# Power_PCB.net
KiCad netlist of a schematic drawn in EAGLE
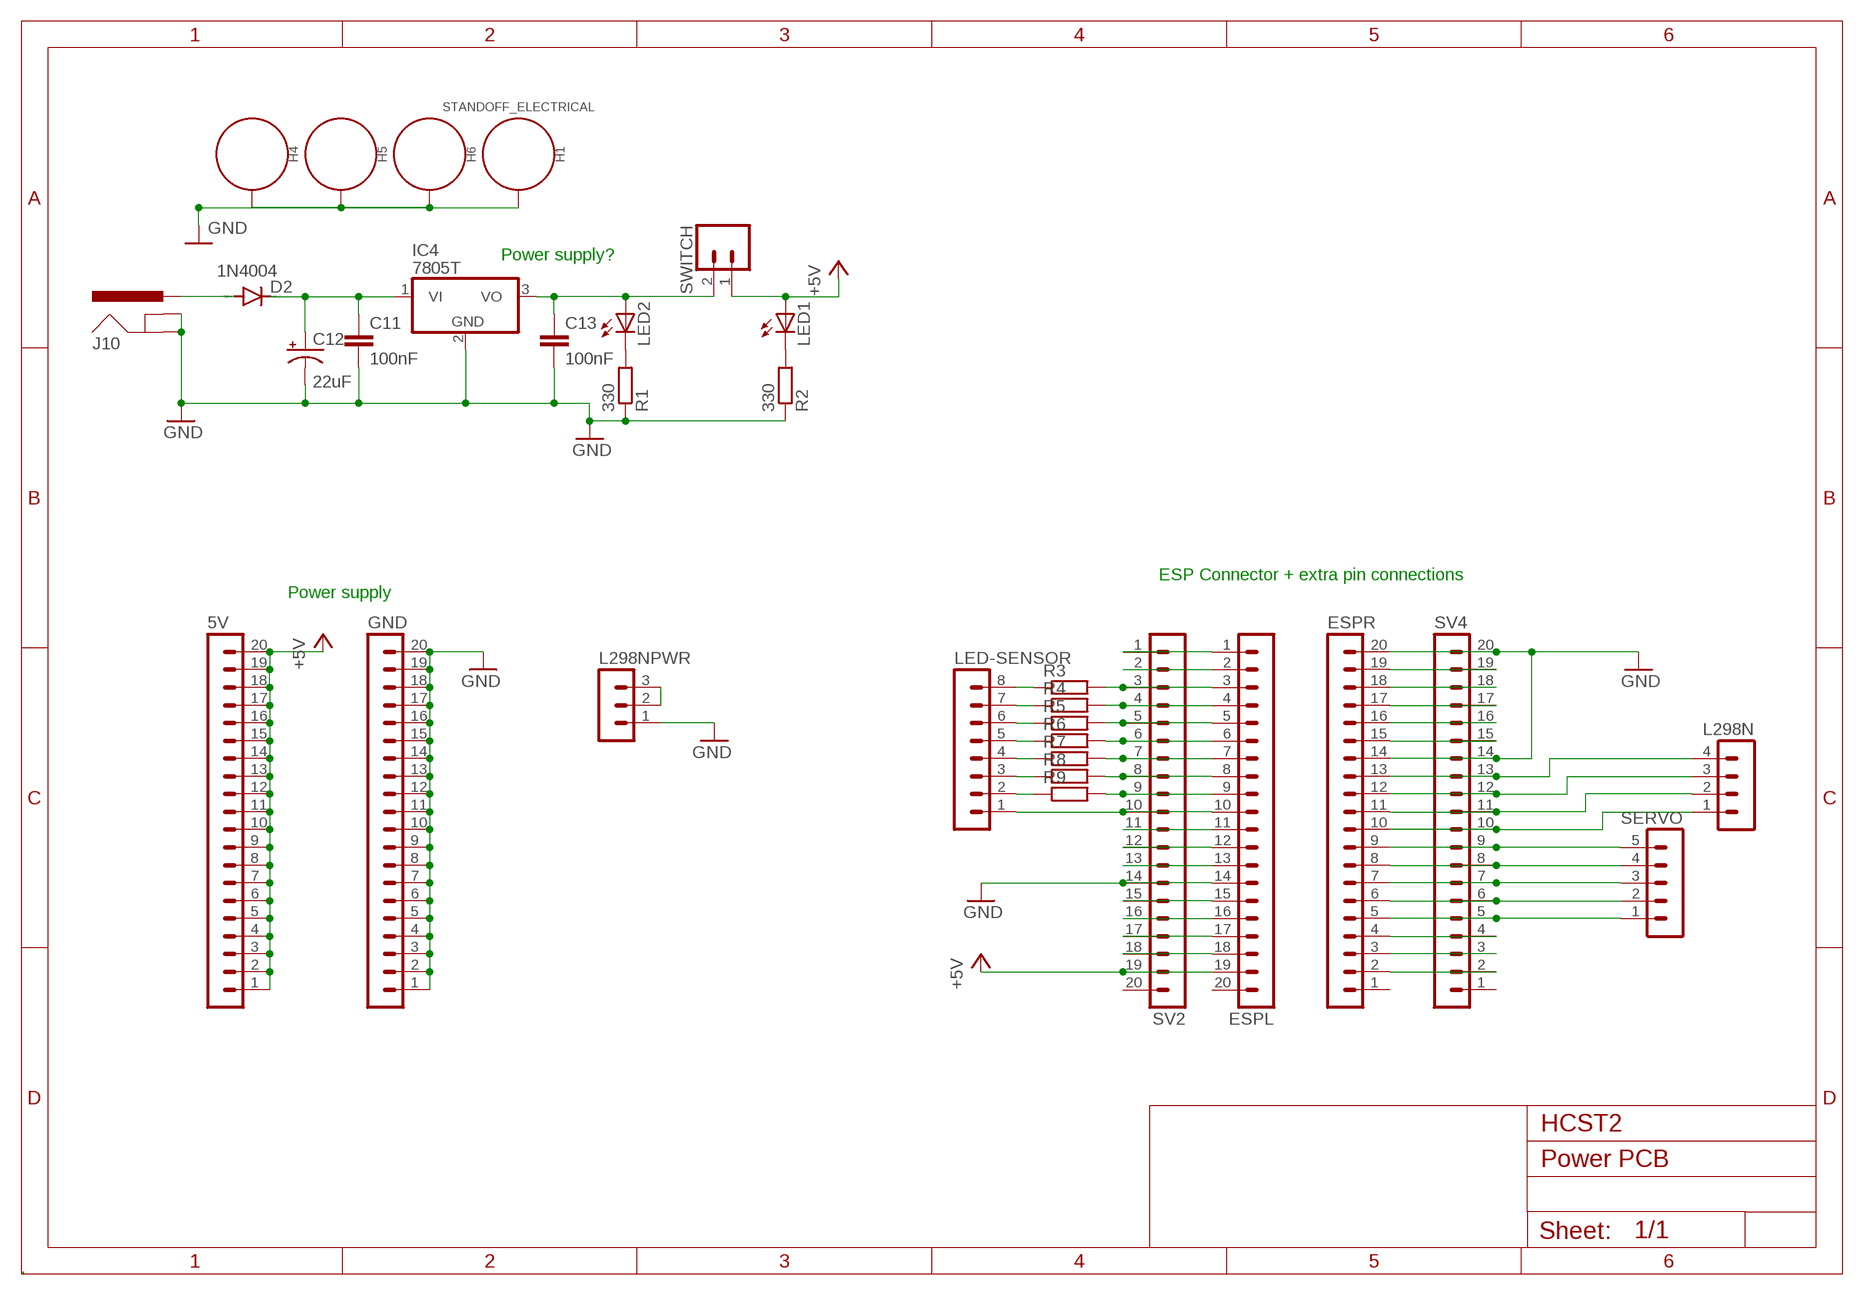
[diagram p0: schematic, sheet 1]

(export (version "E")
  (design (tool "Eeschema 10.0.6"))
  (components
    (comp (ref "5V")
      (value "MA20-1")
      (footprint "eagle-import:MA20-1")
      (libsource (lib "eagle-import") (part "MA20-1"))
    )
    (comp (ref "C11")
      (value "100nF")
      (footprint "eagle-import:C2.5-2")
      (libsource (lib "eagle-import") (part "C2.5/2"))
    )
    (comp (ref "C12")
      (value "22uF")
      (footprint "eagle-import:E2,5-7")
      (libsource (lib "eagle-import") (part "CPOL-USE2.5-7"))
    )
    (comp (ref "C13")
      (value "100nF")
      (footprint "eagle-import:C2.5-2")
      (libsource (lib "eagle-import") (part "C2.5/2"))
    )
    (comp (ref "D2")
      (value "1N4004")
      (footprint "eagle-import:DO41-10")
      (libsource (lib "eagle-import") (part "1N4004"))
    )
    (comp (ref "ESPL")
      (value "MA20-1")
      (footprint "eagle-import:MA20-1")
      (libsource (lib "eagle-import") (part "MA20-1"))
    )
    (comp (ref "ESPR")
      (value "MA20-1")
      (footprint "eagle-import:MA20-1")
      (libsource (lib "eagle-import") (part "MA20-1"))
    )
    (comp (ref "GND")
      (value "MA20-1")
      (footprint "eagle-import:MA20-1")
      (libsource (lib "eagle-import") (part "MA20-1"))
    )
    (comp (ref "H1")
      (value "STANDOFF_ELECTRICAL")
      (footprint "eagle-import:STANDOFF-ELECTRICAL")
      (libsource (lib "eagle-import") (part "STANDOFF_ELECTRICAL"))
    )
    (comp (ref "H4")
      (value "STANDOFF_ELECTRICAL")
      (footprint "eagle-import:STANDOFF-ELECTRICAL")
      (libsource (lib "eagle-import") (part "SparkFun-Hardware_519_STANDOFF_ELECTRICAL"))
    )
    (comp (ref "H5")
      (value "STANDOFF_ELECTRICAL")
      (footprint "eagle-import:STANDOFF-ELECTRICAL")
      (libsource (lib "eagle-import") (part "SparkFun-Hardware_519_STANDOFF_ELECTRICAL"))
    )
    (comp (ref "H6")
      (value "STANDOFF_ELECTRICAL")
      (footprint "eagle-import:STANDOFF-ELECTRICAL")
      (libsource (lib "eagle-import") (part "SparkFun-Hardware_519_STANDOFF_ELECTRICAL"))
    )
    (comp (ref "IC4")
      (value "7805T")
      (footprint "eagle-import:TO220H")
      (libsource (lib "eagle-import") (part "78T05"))
    )
    (comp (ref "J10")
      (value "EL311-ROBOT_SPARKFUN-CONNECTORS_POWER_JACKPTH")
      (footprint "eagle-import:EL311-ROBOT_SPARKFUN-CONNECTORS_POWER_JACK_PTH")
      (libsource (lib "eagle-import") (part "EL311-ROBOT_SPARKFUN-CONNECTORS_POWER_JACKPTH"))
    )
    (comp (ref "L298N")
      (value "MA04-1")
      (footprint "eagle-import:MA04-1")
      (libsource (lib "eagle-import") (part "MA04-1"))
    )
    (comp (ref "L298NPWR")
      (value "MA03-1")
      (footprint "eagle-import:MA03-1")
      (libsource (lib "eagle-import") (part "MA03-1"))
    )
    (comp (ref "LED-SENSOR")
      (value "MA08-1")
      (footprint "eagle-import:MA08-1")
      (libsource (lib "eagle-import") (part "MA08-1"))
    )
    (comp (ref "LED1")
      (value "LED3MM")
      (footprint "eagle-import:LED3MM")
      (libsource (lib "eagle-import") (part "LED3MM"))
    )
    (comp (ref "LED2")
      (value "LED3MM")
      (footprint "eagle-import:LED3MM")
      (libsource (lib "eagle-import") (part "LED3MM"))
    )
    (comp (ref "R1")
      (value "330")
      (footprint "eagle-import:0207_10")
      (libsource (lib "eagle-import") (part "R-EU_0207/10"))
    )
    (comp (ref "R2")
      (value "330")
      (footprint "eagle-import:0207_10")
      (libsource (lib "eagle-import") (part "R-EU_0207/10"))
    )
    (comp (ref "R3")
      (value "R-EU_0207/10")
      (footprint "eagle-import:0207_10")
      (libsource (lib "eagle-import") (part "R-EU_0207/10"))
    )
    (comp (ref "R4")
      (value "R-EU_0207/10")
      (footprint "eagle-import:0207_10")
      (libsource (lib "eagle-import") (part "R-EU_0207/10"))
    )
    (comp (ref "R5")
      (value "R-EU_0207/10")
      (footprint "eagle-import:0207_10")
      (libsource (lib "eagle-import") (part "R-EU_0207/10"))
    )
    (comp (ref "R6")
      (value "R-EU_0207/10")
      (footprint "eagle-import:0207_10")
      (libsource (lib "eagle-import") (part "R-EU_0207/10"))
    )
    (comp (ref "R7")
      (value "R-EU_0207/10")
      (footprint "eagle-import:0207_10")
      (libsource (lib "eagle-import") (part "R-EU_0207/10"))
    )
    (comp (ref "R8")
      (value "R-EU_0207/10")
      (footprint "eagle-import:0207_10")
      (libsource (lib "eagle-import") (part "R-EU_0207/10"))
    )
    (comp (ref "R9")
      (value "R-EU_0207/10")
      (footprint "eagle-import:0207_10")
      (libsource (lib "eagle-import") (part "R-EU_0207/10"))
    )
    (comp (ref "SERVO")
      (value "MA05-1")
      (footprint "eagle-import:MA05-1")
      (libsource (lib "eagle-import") (part "MA05-1"))
    )
    (comp (ref "SV2")
      (value "MA20-1")
      (footprint "eagle-import:MA20-1")
      (libsource (lib "eagle-import") (part "MA20-1"))
    )
    (comp (ref "SV4")
      (value "MA20-1")
      (footprint "eagle-import:MA20-1")
      (libsource (lib "eagle-import") (part "MA20-1"))
    )
    (comp (ref "SWITCH")
      (value "CONN_02")
      (footprint "eagle-import:1X02")
      (libsource (lib "eagle-import") (part "CONN_02"))
    )
  )
  (nets
    (net (code "1") (name "+5V") (class "Default")
      (node (ref "5V") (pin "1") (pinfunction "1_1") (pintype "passive"))
      (node (ref "5V") (pin "10") (pinfunction "10_10") (pintype "passive"))
      (node (ref "5V") (pin "11") (pinfunction "11_11") (pintype "passive"))
      (node (ref "5V") (pin "12") (pinfunction "12_12") (pintype "passive"))
      (node (ref "5V") (pin "13") (pinfunction "13_13") (pintype "passive"))
      (node (ref "5V") (pin "14") (pinfunction "14_14") (pintype "passive"))
      (node (ref "5V") (pin "15") (pinfunction "15_15") (pintype "passive"))
      (node (ref "5V") (pin "16") (pinfunction "16_16") (pintype "passive"))
      (node (ref "5V") (pin "17") (pinfunction "17_17") (pintype "passive"))
      (node (ref "5V") (pin "18") (pinfunction "18_18") (pintype "passive"))
      (node (ref "5V") (pin "19") (pinfunction "19_19") (pintype "passive"))
      (node (ref "5V") (pin "2") (pinfunction "2_2") (pintype "passive"))
      (node (ref "5V") (pin "20") (pinfunction "20_20") (pintype "passive"))
      (node (ref "5V") (pin "3") (pinfunction "3_3") (pintype "passive"))
      (node (ref "5V") (pin "4") (pinfunction "4_4") (pintype "passive"))
      (node (ref "5V") (pin "5") (pinfunction "5_5") (pintype "passive"))
      (node (ref "5V") (pin "6") (pinfunction "6_6") (pintype "passive"))
      (node (ref "5V") (pin "7") (pinfunction "7_7") (pintype "passive"))
      (node (ref "5V") (pin "8") (pinfunction "8_8") (pintype "passive"))
      (node (ref "5V") (pin "9") (pinfunction "9_9") (pintype "passive"))
      (node (ref "ESPL") (pin "19") (pinfunction "19_19") (pintype "passive"))
      (node (ref "LED1") (pin "A") (pinfunction "A_A") (pintype "passive"))
      (node (ref "SV2") (pin "19") (pinfunction "19_19") (pintype "passive"))
      (node (ref "SWITCH") (pin "1") (pinfunction "1_1") (pintype "passive"))
    )
    (net (code "2") (name "GND") (class "Default")
      (node (ref "C11") (pin "2") (pinfunction "2_2") (pintype "passive"))
      (node (ref "C12") (pin "-") (pinfunction "-_-") (pintype "passive"))
      (node (ref "C13") (pin "2") (pinfunction "2_2") (pintype "passive"))
      (node (ref "ESPL") (pin "14") (pinfunction "14_14") (pintype "passive"))
      (node (ref "ESPR") (pin "14") (pinfunction "14_14") (pintype "passive"))
      (node (ref "ESPR") (pin "20") (pinfunction "20_20") (pintype "passive"))
      (node (ref "GND") (pin "1") (pinfunction "1_1") (pintype "passive"))
      (node (ref "GND") (pin "10") (pinfunction "10_10") (pintype "passive"))
      (node (ref "GND") (pin "11") (pinfunction "11_11") (pintype "passive"))
      (node (ref "GND") (pin "12") (pinfunction "12_12") (pintype "passive"))
      (node (ref "GND") (pin "13") (pinfunction "13_13") (pintype "passive"))
      (node (ref "GND") (pin "14") (pinfunction "14_14") (pintype "passive"))
      (node (ref "GND") (pin "15") (pinfunction "15_15") (pintype "passive"))
      (node (ref "GND") (pin "16") (pinfunction "16_16") (pintype "passive"))
      (node (ref "GND") (pin "17") (pinfunction "17_17") (pintype "passive"))
      (node (ref "GND") (pin "18") (pinfunction "18_18") (pintype "passive"))
      (node (ref "GND") (pin "19") (pinfunction "19_19") (pintype "passive"))
      (node (ref "GND") (pin "2") (pinfunction "2_2") (pintype "passive"))
      (node (ref "GND") (pin "20") (pinfunction "20_20") (pintype "passive"))
      (node (ref "GND") (pin "3") (pinfunction "3_3") (pintype "passive"))
      (node (ref "GND") (pin "4") (pinfunction "4_4") (pintype "passive"))
      (node (ref "GND") (pin "5") (pinfunction "5_5") (pintype "passive"))
      (node (ref "GND") (pin "6") (pinfunction "6_6") (pintype "passive"))
      (node (ref "GND") (pin "7") (pinfunction "7_7") (pintype "passive"))
      (node (ref "GND") (pin "8") (pinfunction "8_8") (pintype "passive"))
      (node (ref "GND") (pin "9") (pinfunction "9_9") (pintype "passive"))
      (node (ref "H1") (pin "P1") (pinfunction "P$1_P1") (pintype "bidirectional"))
      (node (ref "H4") (pin "P1") (pinfunction "P$1_P1") (pintype "bidirectional"))
      (node (ref "H5") (pin "P1") (pinfunction "P$1_P1") (pintype "bidirectional"))
      (node (ref "H6") (pin "P1") (pinfunction "P$1_P1") (pintype "bidirectional"))
      (node (ref "IC4") (pin "2") (pinfunction "GND_2") (pintype "passive"))
      (node (ref "J10") (pin "GND") (pinfunction "GND_GND") (pintype "bidirectional"))
      (node (ref "J10") (pin "GNDBREAK") (pinfunction "GNDBREAK_GNDBREAK") (pintype "bidirectional"))
      (node (ref "L298NPWR") (pin "1") (pinfunction "1_1") (pintype "passive"))
      (node (ref "R1") (pin "1") (pinfunction "1_1") (pintype "passive"))
      (node (ref "R2") (pin "1") (pinfunction "1_1") (pintype "passive"))
      (node (ref "SV2") (pin "14") (pinfunction "14_14") (pintype "passive"))
      (node (ref "SV4") (pin "14") (pinfunction "14_14") (pintype "passive"))
      (node (ref "SV4") (pin "20") (pinfunction "20_20") (pintype "passive"))
    )
    (net (code "3") (name "Net-(D2-PadA)") (class "Default")
      (node (ref "D2") (pin "A") (pinfunction "A_A") (pintype "passive"))
      (node (ref "J10") (pin "PWR") (pinfunction "PWR_PWR") (pintype "bidirectional"))
    )
    (net (code "4") (name "Net-(ESPL-Pad1)") (class "Default")
      (node (ref "ESPL") (pin "1") (pinfunction "1_1") (pintype "passive"))
      (node (ref "SV2") (pin "1") (pinfunction "1_1") (pintype "passive"))
    )
    (net (code "5") (name "Net-(ESPL-Pad2)") (class "Default")
      (node (ref "ESPL") (pin "2") (pinfunction "2_2") (pintype "passive"))
      (node (ref "SV2") (pin "2") (pinfunction "2_2") (pintype "passive"))
    )
    (net (code "6") (name "Net-(ESPL-Pad3)") (class "Default")
      (node (ref "ESPL") (pin "3") (pinfunction "3_3") (pintype "passive"))
      (node (ref "R3") (pin "2") (pinfunction "2_2") (pintype "passive"))
      (node (ref "SV2") (pin "3") (pinfunction "3_3") (pintype "passive"))
    )
    (net (code "7") (name "Net-(ESPL-Pad4)") (class "Default")
      (node (ref "ESPL") (pin "4") (pinfunction "4_4") (pintype "passive"))
      (node (ref "R4") (pin "2") (pinfunction "2_2") (pintype "passive"))
      (node (ref "SV2") (pin "4") (pinfunction "4_4") (pintype "passive"))
    )
    (net (code "8") (name "Net-(ESPL-Pad5)") (class "Default")
      (node (ref "ESPL") (pin "5") (pinfunction "5_5") (pintype "passive"))
      (node (ref "R5") (pin "2") (pinfunction "2_2") (pintype "passive"))
      (node (ref "SV2") (pin "5") (pinfunction "5_5") (pintype "passive"))
    )
    (net (code "9") (name "Net-(ESPL-Pad6)") (class "Default")
      (node (ref "ESPL") (pin "6") (pinfunction "6_6") (pintype "passive"))
      (node (ref "R6") (pin "2") (pinfunction "2_2") (pintype "passive"))
      (node (ref "SV2") (pin "6") (pinfunction "6_6") (pintype "passive"))
    )
    (net (code "10") (name "Net-(ESPL-Pad7)") (class "Default")
      (node (ref "ESPL") (pin "7") (pinfunction "7_7") (pintype "passive"))
      (node (ref "R7") (pin "2") (pinfunction "2_2") (pintype "passive"))
      (node (ref "SV2") (pin "7") (pinfunction "7_7") (pintype "passive"))
    )
    (net (code "11") (name "Net-(ESPL-Pad8)") (class "Default")
      (node (ref "ESPL") (pin "8") (pinfunction "8_8") (pintype "passive"))
      (node (ref "R8") (pin "2") (pinfunction "2_2") (pintype "passive"))
      (node (ref "SV2") (pin "8") (pinfunction "8_8") (pintype "passive"))
    )
    (net (code "12") (name "Net-(ESPL-Pad9)") (class "Default")
      (node (ref "ESPL") (pin "9") (pinfunction "9_9") (pintype "passive"))
      (node (ref "R9") (pin "2") (pinfunction "2_2") (pintype "passive"))
      (node (ref "SV2") (pin "9") (pinfunction "9_9") (pintype "passive"))
    )
    (net (code "13") (name "Net-(ESPL-Pad10)") (class "Default")
      (node (ref "ESPL") (pin "10") (pinfunction "10_10") (pintype "passive"))
      (node (ref "LED-SENSOR") (pin "1") (pinfunction "1_1") (pintype "passive"))
      (node (ref "SV2") (pin "10") (pinfunction "10_10") (pintype "passive"))
    )
    (net (code "14") (name "Net-(ESPL-Pad11)") (class "Default")
      (node (ref "ESPL") (pin "11") (pinfunction "11_11") (pintype "passive"))
      (node (ref "SV2") (pin "11") (pinfunction "11_11") (pintype "passive"))
    )
    (net (code "15") (name "Net-(ESPL-Pad12)") (class "Default")
      (node (ref "ESPL") (pin "12") (pinfunction "12_12") (pintype "passive"))
      (node (ref "SV2") (pin "12") (pinfunction "12_12") (pintype "passive"))
    )
    (net (code "16") (name "Net-(ESPL-Pad13)") (class "Default")
      (node (ref "ESPL") (pin "13") (pinfunction "13_13") (pintype "passive"))
      (node (ref "SV2") (pin "13") (pinfunction "13_13") (pintype "passive"))
    )
    (net (code "17") (name "Net-(ESPL-Pad15)") (class "Default")
      (node (ref "ESPL") (pin "15") (pinfunction "15_15") (pintype "passive"))
      (node (ref "SV2") (pin "15") (pinfunction "15_15") (pintype "passive"))
    )
    (net (code "18") (name "Net-(ESPL-Pad16)") (class "Default")
      (node (ref "ESPL") (pin "16") (pinfunction "16_16") (pintype "passive"))
      (node (ref "SV2") (pin "16") (pinfunction "16_16") (pintype "passive"))
    )
    (net (code "19") (name "Net-(ESPL-Pad17)") (class "Default")
      (node (ref "ESPL") (pin "17") (pinfunction "17_17") (pintype "passive"))
      (node (ref "SV2") (pin "17") (pinfunction "17_17") (pintype "passive"))
    )
    (net (code "20") (name "Net-(ESPL-Pad18)") (class "Default")
      (node (ref "ESPL") (pin "18") (pinfunction "18_18") (pintype "passive"))
      (node (ref "SV2") (pin "18") (pinfunction "18_18") (pintype "passive"))
    )
    (net (code "21") (name "Net-(ESPR-Pad2)") (class "Default")
      (node (ref "ESPR") (pin "2") (pinfunction "2_2") (pintype "passive"))
      (node (ref "SV4") (pin "2") (pinfunction "2_2") (pintype "passive"))
    )
    (net (code "22") (name "Net-(ESPR-Pad3)") (class "Default")
      (node (ref "ESPR") (pin "3") (pinfunction "3_3") (pintype "passive"))
      (node (ref "SV4") (pin "3") (pinfunction "3_3") (pintype "passive"))
    )
    (net (code "23") (name "Net-(ESPR-Pad4)") (class "Default")
      (node (ref "ESPR") (pin "4") (pinfunction "4_4") (pintype "passive"))
      (node (ref "SV4") (pin "4") (pinfunction "4_4") (pintype "passive"))
    )
    (net (code "24") (name "Net-(ESPR-Pad5)") (class "Default")
      (node (ref "ESPR") (pin "5") (pinfunction "5_5") (pintype "passive"))
      (node (ref "SERVO") (pin "1") (pinfunction "1_1") (pintype "passive"))
      (node (ref "SV4") (pin "5") (pinfunction "5_5") (pintype "passive"))
    )
    (net (code "25") (name "Net-(ESPR-Pad6)") (class "Default")
      (node (ref "ESPR") (pin "6") (pinfunction "6_6") (pintype "passive"))
      (node (ref "SERVO") (pin "2") (pinfunction "2_2") (pintype "passive"))
      (node (ref "SV4") (pin "6") (pinfunction "6_6") (pintype "passive"))
    )
    (net (code "26") (name "Net-(ESPR-Pad7)") (class "Default")
      (node (ref "ESPR") (pin "7") (pinfunction "7_7") (pintype "passive"))
      (node (ref "SERVO") (pin "3") (pinfunction "3_3") (pintype "passive"))
      (node (ref "SV4") (pin "7") (pinfunction "7_7") (pintype "passive"))
    )
    (net (code "27") (name "Net-(ESPR-Pad8)") (class "Default")
      (node (ref "ESPR") (pin "8") (pinfunction "8_8") (pintype "passive"))
      (node (ref "SERVO") (pin "4") (pinfunction "4_4") (pintype "passive"))
      (node (ref "SV4") (pin "8") (pinfunction "8_8") (pintype "passive"))
    )
    (net (code "28") (name "Net-(ESPR-Pad9)") (class "Default")
      (node (ref "ESPR") (pin "9") (pinfunction "9_9") (pintype "passive"))
      (node (ref "SERVO") (pin "5") (pinfunction "5_5") (pintype "passive"))
      (node (ref "SV4") (pin "9") (pinfunction "9_9") (pintype "passive"))
    )
    (net (code "29") (name "Net-(ESPR-Pad10)") (class "Default")
      (node (ref "ESPR") (pin "10") (pinfunction "10_10") (pintype "passive"))
      (node (ref "L298N") (pin "1") (pinfunction "1_1") (pintype "passive"))
      (node (ref "SV4") (pin "10") (pinfunction "10_10") (pintype "passive"))
    )
    (net (code "30") (name "Net-(ESPR-Pad11)") (class "Default")
      (node (ref "ESPR") (pin "11") (pinfunction "11_11") (pintype "passive"))
      (node (ref "L298N") (pin "2") (pinfunction "2_2") (pintype "passive"))
      (node (ref "SV4") (pin "11") (pinfunction "11_11") (pintype "passive"))
    )
    (net (code "31") (name "Net-(ESPR-Pad12)") (class "Default")
      (node (ref "ESPR") (pin "12") (pinfunction "12_12") (pintype "passive"))
      (node (ref "L298N") (pin "3") (pinfunction "3_3") (pintype "passive"))
      (node (ref "SV4") (pin "12") (pinfunction "12_12") (pintype "passive"))
    )
    (net (code "32") (name "Net-(ESPR-Pad13)") (class "Default")
      (node (ref "ESPR") (pin "13") (pinfunction "13_13") (pintype "passive"))
      (node (ref "L298N") (pin "4") (pinfunction "4_4") (pintype "passive"))
      (node (ref "SV4") (pin "13") (pinfunction "13_13") (pintype "passive"))
    )
    (net (code "33") (name "Net-(ESPR-Pad15)") (class "Default")
      (node (ref "ESPR") (pin "15") (pinfunction "15_15") (pintype "passive"))
      (node (ref "SV4") (pin "15") (pinfunction "15_15") (pintype "passive"))
    )
    (net (code "34") (name "Net-(ESPR-Pad16)") (class "Default")
      (node (ref "ESPR") (pin "16") (pinfunction "16_16") (pintype "passive"))
      (node (ref "SV4") (pin "16") (pinfunction "16_16") (pintype "passive"))
    )
    (net (code "35") (name "Net-(ESPR-Pad17)") (class "Default")
      (node (ref "ESPR") (pin "17") (pinfunction "17_17") (pintype "passive"))
      (node (ref "SV4") (pin "17") (pinfunction "17_17") (pintype "passive"))
    )
    (net (code "36") (name "Net-(ESPR-Pad18)") (class "Default")
      (node (ref "ESPR") (pin "18") (pinfunction "18_18") (pintype "passive"))
      (node (ref "SV4") (pin "18") (pinfunction "18_18") (pintype "passive"))
    )
    (net (code "37") (name "Net-(ESPR-Pad19)") (class "Default")
      (node (ref "ESPR") (pin "19") (pinfunction "19_19") (pintype "passive"))
      (node (ref "SV4") (pin "19") (pinfunction "19_19") (pintype "passive"))
    )
    (net (code "38") (name "Net-(IC4-VI)") (class "Default")
      (node (ref "C11") (pin "1") (pinfunction "1_1") (pintype "passive"))
      (node (ref "C12") (pin "+") (pinfunction "+_+") (pintype "passive"))
      (node (ref "D2") (pin "C") (pinfunction "C_C") (pintype "passive"))
      (node (ref "IC4") (pin "1") (pinfunction "VI_1") (pintype "input"))
    )
    (net (code "39") (name "Net-(IC4-VO)") (class "Default")
      (node (ref "C13") (pin "1") (pinfunction "1_1") (pintype "passive"))
      (node (ref "IC4") (pin "3") (pinfunction "VO_3") (pintype "passive"))
      (node (ref "LED2") (pin "A") (pinfunction "A_A") (pintype "passive"))
      (node (ref "SWITCH") (pin "2") (pinfunction "2_2") (pintype "passive"))
    )
    (net (code "40") (name "Net-(L298NPWR-Pad2)") (class "Default")
      (node (ref "L298NPWR") (pin "2") (pinfunction "2_2") (pintype "passive"))
      (node (ref "L298NPWR") (pin "3") (pinfunction "3_3") (pintype "passive"))
    )
    (net (code "41") (name "Net-(LED-SENSOR-Pad2)") (class "Default")
      (node (ref "LED-SENSOR") (pin "2") (pinfunction "2_2") (pintype "passive"))
      (node (ref "R9") (pin "1") (pinfunction "1_1") (pintype "passive"))
    )
    (net (code "42") (name "Net-(LED-SENSOR-Pad3)") (class "Default")
      (node (ref "LED-SENSOR") (pin "3") (pinfunction "3_3") (pintype "passive"))
      (node (ref "R8") (pin "1") (pinfunction "1_1") (pintype "passive"))
    )
    (net (code "43") (name "Net-(LED-SENSOR-Pad4)") (class "Default")
      (node (ref "LED-SENSOR") (pin "4") (pinfunction "4_4") (pintype "passive"))
      (node (ref "R7") (pin "1") (pinfunction "1_1") (pintype "passive"))
    )
    (net (code "44") (name "Net-(LED-SENSOR-Pad5)") (class "Default")
      (node (ref "LED-SENSOR") (pin "5") (pinfunction "5_5") (pintype "passive"))
      (node (ref "R6") (pin "1") (pinfunction "1_1") (pintype "passive"))
    )
    (net (code "45") (name "Net-(LED-SENSOR-Pad6)") (class "Default")
      (node (ref "LED-SENSOR") (pin "6") (pinfunction "6_6") (pintype "passive"))
      (node (ref "R5") (pin "1") (pinfunction "1_1") (pintype "passive"))
    )
    (net (code "46") (name "Net-(LED-SENSOR-Pad7)") (class "Default")
      (node (ref "LED-SENSOR") (pin "7") (pinfunction "7_7") (pintype "passive"))
      (node (ref "R4") (pin "1") (pinfunction "1_1") (pintype "passive"))
    )
    (net (code "47") (name "Net-(LED-SENSOR-Pad8)") (class "Default")
      (node (ref "LED-SENSOR") (pin "8") (pinfunction "8_8") (pintype "passive"))
      (node (ref "R3") (pin "1") (pinfunction "1_1") (pintype "passive"))
    )
    (net (code "48") (name "Net-(LED1-C)") (class "Default")
      (node (ref "LED1") (pin "K") (pinfunction "C_K") (pintype "passive"))
      (node (ref "R2") (pin "2") (pinfunction "2_2") (pintype "passive"))
    )
    (net (code "49") (name "Net-(LED2-C)") (class "Default")
      (node (ref "LED2") (pin "K") (pinfunction "C_K") (pintype "passive"))
      (node (ref "R1") (pin "2") (pinfunction "2_2") (pintype "passive"))
    )
    (net (code "50") (name "unconnected-(ESPL-Pad20)") (class "Default")
      (node (ref "ESPL") (pin "20") (pinfunction "20_20") (pintype "passive"))
    )
    (net (code "51") (name "unconnected-(ESPR-Pad1)") (class "Default")
      (node (ref "ESPR") (pin "1") (pinfunction "1_1") (pintype "passive"))
    )
    (net (code "52") (name "unconnected-(SV2-Pad20)") (class "Default")
      (node (ref "SV2") (pin "20") (pinfunction "20_20") (pintype "passive"))
    )
    (net (code "53") (name "unconnected-(SV4-Pad1)") (class "Default")
      (node (ref "SV4") (pin "1") (pinfunction "1_1") (pintype "passive"))
    )
  )
)
